# stampede-board.net
KiCad netlist of a schematic drawn in EAGLE
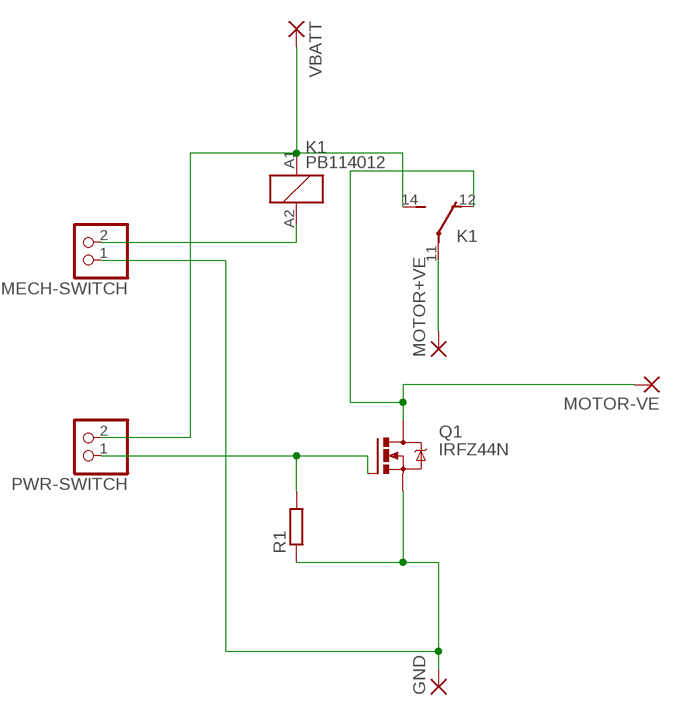
[diagram p0: schematic, sheet 1]

(export (version "E")
  (design (tool "Eeschema 10.0.6"))
  (components
    (comp (ref "GND")
      (value "WIREPAD3,17/1,3")
      (footprint "eagle-import:3,17_1,3")
      (libsource (lib "eagle-import") (part "WIREPAD3,17/1,3"))
    )
    (comp (ref "K1")
      (value "PB114012")
      (footprint "eagle-import:PB")
      (fields (field (name "MF") "TYCO ELECTRONICS"))
      (libsource (lib "eagle-import") (part "PB?141012"))
    )
    (comp (ref "MECH-SWITCH")
      (value "PINHD-1X2")
      (footprint "eagle-import:1X02")
      (libsource (lib "eagle-import") (part "PINHD-1X2"))
    )
    (comp (ref "MOTOR+VE")
      (value "WIREPAD3,17/1,3")
      (footprint "eagle-import:3,17_1,3")
      (libsource (lib "eagle-import") (part "WIREPAD3,17/1,3"))
    )
    (comp (ref "MOTOR-VE")
      (value "WIREPAD3,17/1,3")
      (footprint "eagle-import:3,17_1,3")
      (libsource (lib "eagle-import") (part "WIREPAD3,17/1,3"))
    )
    (comp (ref "PWR-SWITCH")
      (value "PINHD-1X2")
      (footprint "eagle-import:1X02")
      (libsource (lib "eagle-import") (part "PINHD-1X2"))
    )
    (comp (ref "Q1")
      (value "IRFZ44N")
      (footprint "eagle-import:TO220BV")
      (libsource (lib "eagle-import") (part "IRF520"))
    )
    (comp (ref "R1")
      (value "R-EU_0207/7")
      (footprint "eagle-import:0207_7")
      (libsource (lib "eagle-import") (part "R-EU_0207/7"))
    )
    (comp (ref "VBATT")
      (value "WIREPAD3,17/1,3")
      (footprint "eagle-import:3,17_1,3")
      (libsource (lib "eagle-import") (part "WIREPAD3,17/1,3"))
    )
  )
  (nets
    (net (code "1") (name "Net-(GND-P)") (class "Default")
      (node (ref "GND") (pin "1") (pinfunction "P_1") (pintype "passive"))
      (node (ref "MECH-SWITCH") (pin "1") (pinfunction "1_1") (pintype "passive"))
      (node (ref "Q1") (pin "S") (pinfunction "S_S") (pintype "passive"))
      (node (ref "R1") (pin "1") (pinfunction "1_1") (pintype "passive"))
    )
    (net (code "2") (name "Net-(K1A-1)") (class "Default")
      (node (ref "K1") (pin "14") (pinfunction "S_14") (pintype "passive"))
      (node (ref "K1") (pin "A1") (pinfunction "1_A1") (pintype "passive"))
      (node (ref "PWR-SWITCH") (pin "2") (pinfunction "2_2") (pintype "passive"))
      (node (ref "VBATT") (pin "1") (pinfunction "P_1") (pintype "passive"))
    )
    (net (code "3") (name "Net-(K1A-2)") (class "Default")
      (node (ref "K1") (pin "A2") (pinfunction "2_A2") (pintype "passive"))
      (node (ref "MECH-SWITCH") (pin "2") (pinfunction "2_2") (pintype "passive"))
    )
    (net (code "4") (name "Net-(K1B-O)") (class "Default")
      (node (ref "K1") (pin "12") (pinfunction "O_12") (pintype "passive"))
      (node (ref "MOTOR-VE") (pin "1") (pinfunction "P_1") (pintype "passive"))
      (node (ref "Q1") (pin "D") (pinfunction "D_D") (pintype "passive"))
    )
    (net (code "5") (name "Net-(K1B-P)") (class "Default")
      (node (ref "K1") (pin "11") (pinfunction "P_11") (pintype "passive"))
      (node (ref "MOTOR+VE") (pin "1") (pinfunction "P_1") (pintype "passive"))
    )
    (net (code "6") (name "Net-(PWR-SWITCH-Pad1)") (class "Default")
      (node (ref "PWR-SWITCH") (pin "1") (pinfunction "1_1") (pintype "passive"))
      (node (ref "Q1") (pin "G") (pinfunction "G_G") (pintype "passive"))
      (node (ref "R1") (pin "2") (pinfunction "2_2") (pintype "passive"))
    )
  )
)
